# ampinv.net
KiCad netlist of a schematic drawn in EAGLE
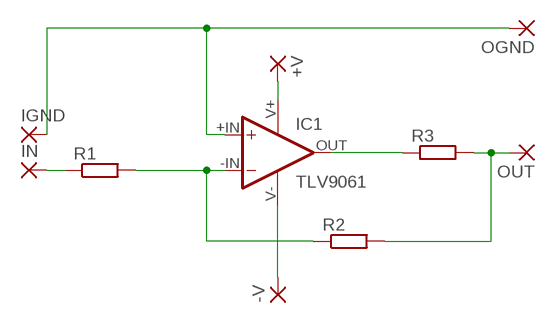
[diagram p0: schematic, sheet 1]

(export (version "E")
  (design (tool "Eeschema 10.0.6"))
  (components
    (comp (ref "+V")
      (value "SMD2")
      (footprint "eagle-import:SMD1,27-2,54")
      (libsource (lib "eagle-import") (part "SMD2"))
    )
    (comp (ref "-V")
      (value "SMD2")
      (footprint "eagle-import:SMD1,27-2,54")
      (libsource (lib "eagle-import") (part "SMD2"))
    )
    (comp (ref "IC1")
      (value "TLV9061")
      (footprint "eagle-import:TLV9061")
      (libsource (lib "eagle-import") (part "TLV9061"))
    )
    (comp (ref "IGND")
      (value "SMD2")
      (footprint "eagle-import:SMD1,27-2,54")
      (libsource (lib "eagle-import") (part "SMD2"))
    )
    (comp (ref "IN")
      (value "SMD2")
      (footprint "eagle-import:SMD1,27-2,54")
      (libsource (lib "eagle-import") (part "SMD2"))
    )
    (comp (ref "OGND")
      (value "SMD2")
      (footprint "eagle-import:SMD1,27-2,54")
      (libsource (lib "eagle-import") (part "SMD2"))
    )
    (comp (ref "OUT")
      (value "SMD2")
      (footprint "eagle-import:SMD1,27-2,54")
      (libsource (lib "eagle-import") (part "SMD2"))
    )
    (comp (ref "R1")
      (value "R-EU_R0402")
      (footprint "eagle-import:R0402")
      (libsource (lib "eagle-import") (part "R-EU_R0402"))
    )
    (comp (ref "R2")
      (value "R-EU_R0402")
      (footprint "eagle-import:R0402")
      (libsource (lib "eagle-import") (part "R-EU_R0402"))
    )
    (comp (ref "R3")
      (value "R-EU_R0402")
      (footprint "eagle-import:R0402")
      (libsource (lib "eagle-import") (part "R-EU_R0402"))
    )
  )
  (nets
    (net (code "1") (name "Net-(+V-P)") (class "Default")
      (node (ref "+V") (pin "1") (pinfunction "P_1") (pintype "passive"))
      (node (ref "IC1") (pin "V+") (pinfunction "V+_V+") (pintype "power_in"))
    )
    (net (code "2") (name "Net-(-V-P)") (class "Default")
      (node (ref "-V") (pin "1") (pinfunction "P_1") (pintype "passive"))
      (node (ref "IC1") (pin "V-") (pinfunction "V-_V-") (pintype "power_in"))
    )
    (net (code "3") (name "Net-(IC1-Pad-IN)") (class "Default")
      (node (ref "IC1") (pin "-IN") (pinfunction "-IN_-IN") (pintype "input"))
      (node (ref "R1") (pin "2") (pinfunction "2_2") (pintype "passive"))
      (node (ref "R2") (pin "1") (pinfunction "1_1") (pintype "passive"))
    )
    (net (code "4") (name "Net-(IC1-PadOUT)") (class "Default")
      (node (ref "IC1") (pin "OUT") (pinfunction "OUT_OUT") (pintype "output"))
      (node (ref "R3") (pin "1") (pinfunction "1_1") (pintype "passive"))
    )
    (net (code "5") (name "Net-(IGND-P)") (class "Default")
      (node (ref "IC1") (pin "+IN") (pinfunction "+IN_+IN") (pintype "input"))
      (node (ref "IGND") (pin "1") (pinfunction "P_1") (pintype "passive"))
      (node (ref "OGND") (pin "1") (pinfunction "P_1") (pintype "passive"))
    )
    (net (code "6") (name "Net-(IN-P)") (class "Default")
      (node (ref "IN") (pin "1") (pinfunction "P_1") (pintype "passive"))
      (node (ref "R1") (pin "1") (pinfunction "1_1") (pintype "passive"))
    )
    (net (code "7") (name "Net-(OUT-P)") (class "Default")
      (node (ref "OUT") (pin "1") (pinfunction "P_1") (pintype "passive"))
      (node (ref "R2") (pin "2") (pinfunction "2_2") (pintype "passive"))
      (node (ref "R3") (pin "2") (pinfunction "2_2") (pintype "passive"))
    )
  )
)
